# ProPrj_51board_2024-12-11.net
KiCad netlist of a schematic drawn in EasyEDA Pro
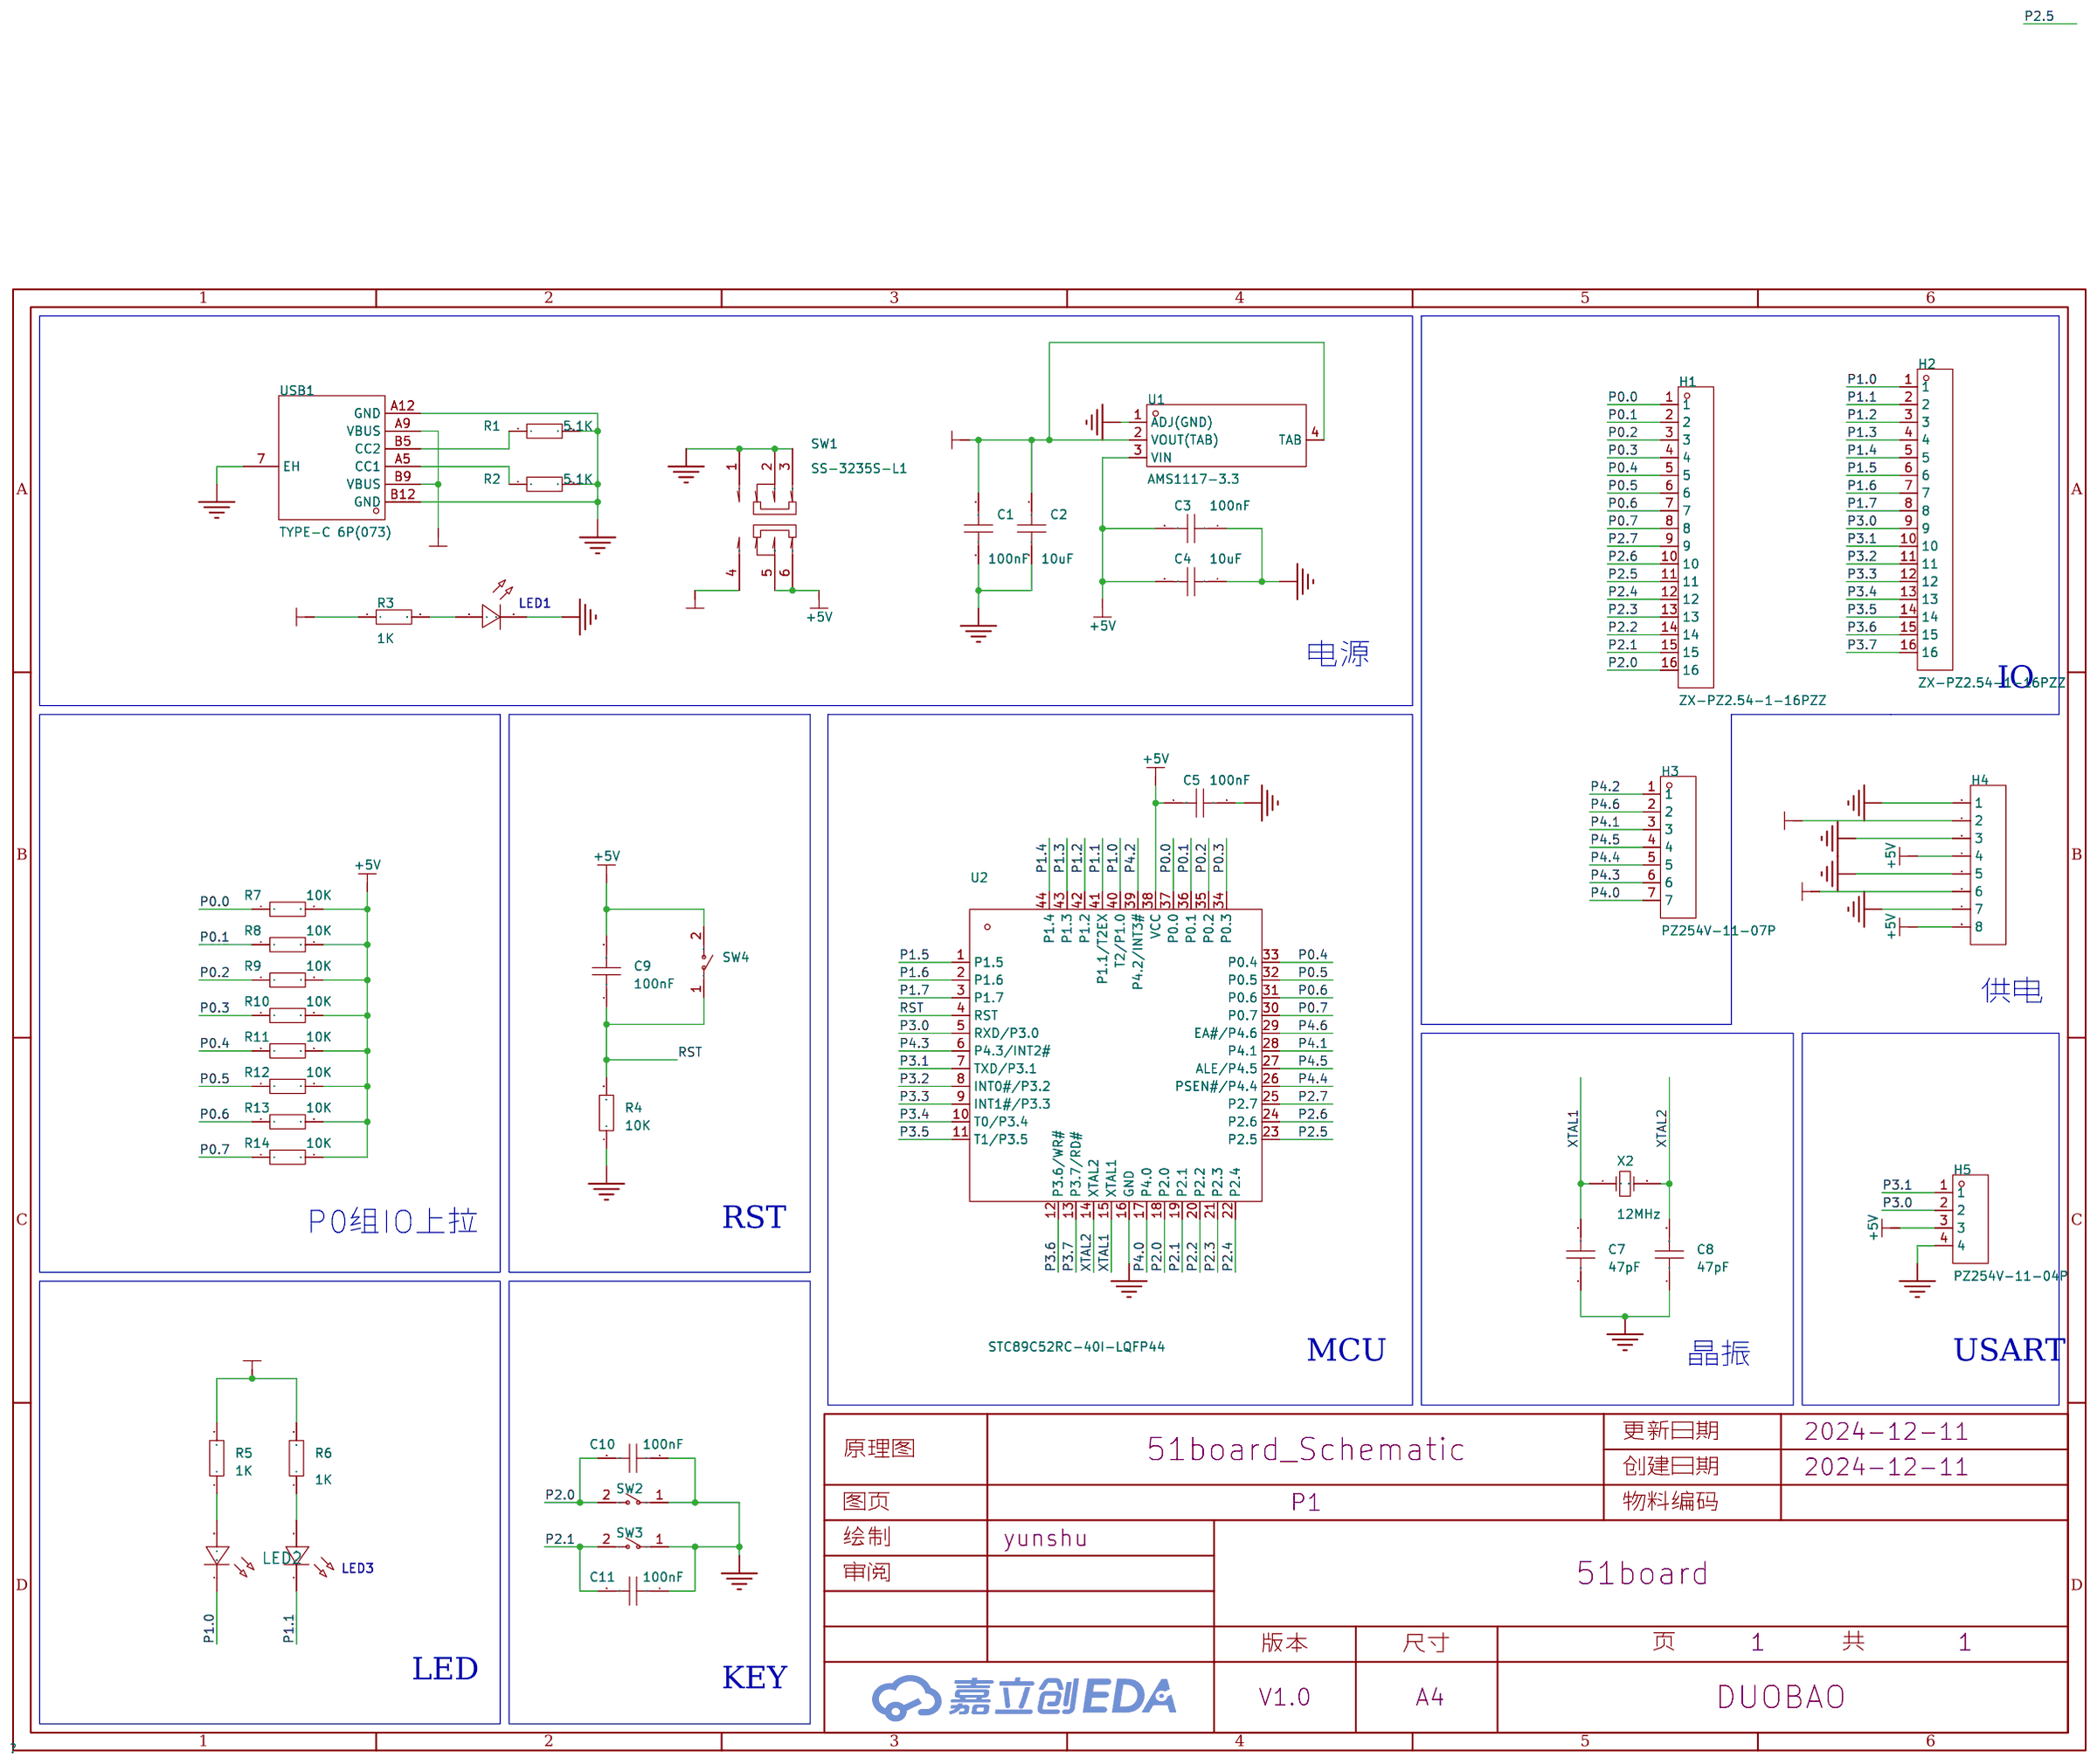
[diagram p0: schematic sheet]

(export (version "E")
  (design (tool "Eeschema 10.0.6"))
  (components
    (comp (ref "C1")
      (value "100nF")
      (footprint "easyedapro:C0603")
      (libsource (lib "easyedapro") (part "CapAcitance"))
    )
    (comp (ref "C2")
      (value "10uF")
      (footprint "easyedapro:C0603")
      (libsource (lib "easyedapro") (part "CapAcitance"))
    )
    (comp (ref "C3")
      (value "100nF")
      (footprint "easyedapro:C0603")
      (libsource (lib "easyedapro") (part "CapAcitance"))
    )
    (comp (ref "C4")
      (value "10uF")
      (footprint "easyedapro:C0603")
      (libsource (lib "easyedapro") (part "CapAcitance"))
    )
    (comp (ref "C5")
      (value "100nF")
      (footprint "easyedapro:C0603")
      (libsource (lib "easyedapro") (part "CapAcitance"))
    )
    (comp (ref "C7")
      (value "47pF")
      (footprint "easyedapro:C0603")
      (libsource (lib "easyedapro") (part "CapAcitance"))
    )
    (comp (ref "C8")
      (value "47pF")
      (footprint "easyedapro:C0603")
      (libsource (lib "easyedapro") (part "CapAcitance"))
    )
    (comp (ref "C9")
      (value "100nF")
      (footprint "easyedapro:C0603")
      (libsource (lib "easyedapro") (part "CapAcitance"))
    )
    (comp (ref "C10")
      (value "100nF")
      (footprint "easyedapro:C0603")
      (libsource (lib "easyedapro") (part "CapAcitance"))
    )
    (comp (ref "C11")
      (value "100nF")
      (footprint "easyedapro:C0603")
      (libsource (lib "easyedapro") (part "CapAcitance"))
    )
    (comp (ref "H1")
      (value "ZX-PZ2.54-1-16PZZ")
      (footprint "easyedapro:HDR-TH_16P-P2.54-V-M")
      (fields (field (name "Manufacturer") "Megastar(兆星)"))
      (libsource (lib "easyedapro") (part "HDR_2.54-1x16P"))
    )
    (comp (ref "H2")
      (value "ZX-PZ2.54-1-16PZZ")
      (footprint "easyedapro:HDR-TH_16P-P2.54-V-M")
      (fields (field (name "Manufacturer") "Megastar(兆星)"))
      (libsource (lib "easyedapro") (part "HDR_2.54-1x16P"))
    )
    (comp (ref "H3")
      (value "PZ254V-11-07P")
      (footprint "easyedapro:HDR-TH_7P-P2.54-V-M")
      (fields (field (name "Manufacturer") "XFCN(兴飞)"))
      (libsource (lib "easyedapro") (part "PZ254V-11-07P"))
    )
    (comp (ref "H4")
      (value "~")
      (footprint "easyedapro:HDR-TH_8P-P2.54-V-F-1")
      (libsource (lib "easyedapro") (part "Header-Female-2.54_1x8"))
    )
    (comp (ref "H5")
      (value "PZ254V-11-04P")
      (footprint "easyedapro:HDR-TH_4P-P2.54-V-M")
      (fields (field (name "Manufacturer") "XFCN(兴飞)"))
      (libsource (lib "easyedapro") (part "PZ254V-11-04P"))
    )
    (comp (ref "LED1")
      (value "~")
      (footprint "easyedapro:LED_0805")
      (libsource (lib "easyedapro") (part "LED_G"))
    )
    (comp (ref "LED2")
      (value "~")
      (footprint "easyedapro:LED_0805")
      (libsource (lib "easyedapro") (part "LED_R"))
    )
    (comp (ref "LED3")
      (value "~")
      (footprint "easyedapro:LED_0805")
      (libsource (lib "easyedapro") (part "LED_B"))
    )
    (comp (ref "R1") (value "5.1K") (footprint "easyedapro:R0805") (libsource (lib "easyedapro") (part "电阻")))
    (comp (ref "R2") (value "5.1K") (footprint "easyedapro:R0805") (libsource (lib "easyedapro") (part "电阻")))
    (comp (ref "R3") (value "1K") (footprint "easyedapro:R0805") (libsource (lib "easyedapro") (part "电阻")))
    (comp (ref "R4") (value "10K") (footprint "easyedapro:R0805") (libsource (lib "easyedapro") (part "电阻")))
    (comp (ref "R5") (value "1K") (footprint "easyedapro:R0805") (libsource (lib "easyedapro") (part "电阻")))
    (comp (ref "R6") (value "1K") (footprint "easyedapro:R0805") (libsource (lib "easyedapro") (part "电阻")))
    (comp (ref "R7") (value "10K") (footprint "easyedapro:R0805") (libsource (lib "easyedapro") (part "电阻")))
    (comp (ref "R8") (value "10K") (footprint "easyedapro:R0805") (libsource (lib "easyedapro") (part "电阻")))
    (comp (ref "R9") (value "10K") (footprint "easyedapro:R0805") (libsource (lib "easyedapro") (part "电阻")))
    (comp (ref "R10") (value "10K") (footprint "easyedapro:R0805") (libsource (lib "easyedapro") (part "电阻")))
    (comp (ref "R11") (value "10K") (footprint "easyedapro:R0805") (libsource (lib "easyedapro") (part "电阻")))
    (comp (ref "R12") (value "10K") (footprint "easyedapro:R0805") (libsource (lib "easyedapro") (part "电阻")))
    (comp (ref "R13") (value "10K") (footprint "easyedapro:R0805") (libsource (lib "easyedapro") (part "电阻")))
    (comp (ref "R14") (value "10K") (footprint "easyedapro:R0805") (libsource (lib "easyedapro") (part "电阻")))
    (comp (ref "SW1")
      (value "SS-3235S-L1")
      (footprint "easyedapro:SW-SMD_SS-3235S-LX")
      (description "电路结构:双刀双掷;安装方式:卧贴;开关颜色:黑色;额定电流(DC):50mA;额定电压(DC):12V;额定电流(AC):50mA;额定电压(AC):12V;机械寿命:1万次;")
      (fields (field (name "Manufacturer") "XKB Connectivity(中国星坤)"))
      (libsource (lib "easyedapro") (part "SS-3235S-L1"))
    )
    (comp (ref "SW2")
      (value "轻触按键 3x6x2.5mm")
      (footprint "easyedapro:SW-SMD_L6.1-W3.7-LS8.0")
      (description "开关长度:6.05mm;开关宽度:3.65mm;开关高度:2.5mm;机械寿命:-;")
      (fields (field (name "Manufacturer") "BBJ"))
      (libsource (lib "easyedapro") (part "轻触按键 3X6X2.5MM"))
    )
    (comp (ref "SW3")
      (value "轻触按键 3x6x2.5mm")
      (footprint "easyedapro:SW-SMD_L6.1-W3.7-LS8.0")
      (description "开关长度:6.05mm;开关宽度:3.65mm;开关高度:2.5mm;机械寿命:-;")
      (fields (field (name "Manufacturer") "BBJ"))
      (libsource (lib "easyedapro") (part "轻触按键 3X6X2.5MM"))
    )
    (comp (ref "SW4")
      (value "轻触按键 3x6x2.5mm")
      (footprint "easyedapro:SW-SMD_L6.1-W3.7-LS8.0")
      (description "开关长度:6.05mm;开关宽度:3.65mm;开关高度:2.5mm;机械寿命:-;")
      (fields (field (name "Manufacturer") "BBJ"))
      (libsource (lib "easyedapro") (part "轻触按键 3X6X2.5MM"))
    )
    (comp (ref "U1")
      (value "AMS1117-3.3")
      (footprint "easyedapro:SOT-223-4_L6.5-W3.5-P2.30-LS7.0-BR")
      (description "输出类型:固定;最大输入电压:18V;输出电压:3.3V;输出电流:1A;电源纹波抑制比(PSRR):60dB@(120Hz);输出极性:正极;")
      (fields (field (name "Manufacturer") "UMW(友台半导体)"))
      (libsource (lib "easyedapro") (part "AMS1117-3.3_C347222"))
    )
    (comp (ref "U2")
      (value "STC89C52RC-40I-LQFP44")
      (footprint "easyedapro:LQFP-44_L10.0-W10.0-P0.80-LS12.0-BL")
      (description "CPU内核:51系列;程序存储容量:8KB;RAM总容量:512Byte;GPIO端口数量:39;工作电压范围:3.3V~5.5V;CPU最大主频:-;程序存储器类型:FLASH;")
      (fields (field (name "Manufacturer") "STC(宏晶)"))
      (libsource (lib "easyedapro") (part "STC89C52RC-40I_C8707"))
    )
    (comp (ref "USB1")
      (value "TYPE-C 6P(073)")
      (footprint "easyedapro:TYPE-C-SMD_TYPE-C-6P_5")
      (description "连接器类型:Type-C;标准:USB 3.1;公母:母;安装方式:卧贴;触点数量:6P;端口数量:1;额定电流 - 电源:3A;工作温度范围:-25°C~+85°C;")
      (fields (field (name "Manufacturer") "SHOU HAN(首韩)"))
      (libsource (lib "easyedapro") (part "TYPE-C 6P(073)"))
    )
    (comp (ref "X2")
      (value "12MHz")
      (footprint "easyedapro:OSC-TH_BD2.0-P0.50")
      (description "晶振类型:直插晶振;频率:12MHz;常温频差:±20ppm;外接负载电容:20pF;频率稳定度(全温):±30ppm;")
      (fields
        (field (name "Manufacturer Part") "TXD12M0002206LDBEO00S")
        (field (name "Manufacturer") "YJX(雅晶鑫)")
      )
      (libsource (lib "easyedapro") (part "TXD12M0002206LDBEO00S"))
    )
  )
  (nets
    (net (code "1") (name "+5V") (class "Default")
      (node (ref "C3") (pin "2") (pinfunction "2_2") (pintype "input"))
      (node (ref "C4") (pin "2") (pinfunction "2_2") (pintype "input"))
      (node (ref "C5") (pin "1") (pinfunction "1_1") (pintype "input"))
      (node (ref "C9") (pin "2") (pinfunction "2_2") (pintype "input"))
      (node (ref "H4") (pin "4") (pinfunction "4_4") (pintype "input"))
      (node (ref "H4") (pin "8") (pinfunction "8_8") (pintype "input"))
      (node (ref "H5") (pin "3") (pinfunction "3_3") (pintype "unspecified"))
      (node (ref "R10") (pin "2") (pinfunction "2_2") (pintype "input"))
      (node (ref "R11") (pin "2") (pinfunction "2_2") (pintype "input"))
      (node (ref "R12") (pin "2") (pinfunction "2_2") (pintype "input"))
      (node (ref "R13") (pin "2") (pinfunction "2_2") (pintype "input"))
      (node (ref "R14") (pin "2") (pinfunction "2_2") (pintype "input"))
      (node (ref "R7") (pin "2") (pinfunction "2_2") (pintype "input"))
      (node (ref "R8") (pin "2") (pinfunction "2_2") (pintype "input"))
      (node (ref "R9") (pin "2") (pinfunction "2_2") (pintype "input"))
      (node (ref "SW1") (pin "5") (pinfunction "5_5") (pintype "unspecified"))
      (node (ref "SW1") (pin "6") (pinfunction "6_6") (pintype "unspecified"))
      (node (ref "SW4") (pin "2") (pinfunction "2_2") (pintype "unspecified"))
      (node (ref "U1") (pin "3") (pinfunction "VIN_3") (pintype "unspecified"))
      (node (ref "U2") (pin "38") (pinfunction "VCC_38") (pintype "unspecified"))
    )
    (net (code "2") (name "/P0.0") (class "Default")
      (node (ref "H1") (pin "1") (pinfunction "1_1") (pintype "input"))
      (node (ref "R7") (pin "1") (pinfunction "1_1") (pintype "input"))
      (node (ref "U2") (pin "37") (pinfunction "P0.0_37") (pintype "unspecified"))
    )
    (net (code "3") (name "/P0.1") (class "Default")
      (node (ref "H1") (pin "2") (pinfunction "2_2") (pintype "input"))
      (node (ref "R8") (pin "1") (pinfunction "1_1") (pintype "input"))
      (node (ref "U2") (pin "36") (pinfunction "P0.1_36") (pintype "unspecified"))
    )
    (net (code "4") (name "/P0.2") (class "Default")
      (node (ref "H1") (pin "3") (pinfunction "3_3") (pintype "input"))
      (node (ref "R9") (pin "1") (pinfunction "1_1") (pintype "input"))
      (node (ref "U2") (pin "35") (pinfunction "P0.2_35") (pintype "unspecified"))
    )
    (net (code "5") (name "/P0.3") (class "Default")
      (node (ref "H1") (pin "4") (pinfunction "4_4") (pintype "input"))
      (node (ref "R10") (pin "1") (pinfunction "1_1") (pintype "input"))
      (node (ref "U2") (pin "34") (pinfunction "P0.3_34") (pintype "unspecified"))
    )
    (net (code "6") (name "/P0.4") (class "Default")
      (node (ref "H1") (pin "5") (pinfunction "5_5") (pintype "input"))
      (node (ref "R11") (pin "1") (pinfunction "1_1") (pintype "input"))
      (node (ref "U2") (pin "33") (pinfunction "P0.4_33") (pintype "unspecified"))
    )
    (net (code "7") (name "/P0.5") (class "Default")
      (node (ref "H1") (pin "6") (pinfunction "6_6") (pintype "input"))
      (node (ref "R12") (pin "1") (pinfunction "1_1") (pintype "input"))
      (node (ref "U2") (pin "32") (pinfunction "P0.5_32") (pintype "unspecified"))
    )
    (net (code "8") (name "/P0.6") (class "Default")
      (node (ref "H1") (pin "7") (pinfunction "7_7") (pintype "input"))
      (node (ref "R13") (pin "1") (pinfunction "1_1") (pintype "input"))
      (node (ref "U2") (pin "31") (pinfunction "P0.6_31") (pintype "unspecified"))
    )
    (net (code "9") (name "/P0.7") (class "Default")
      (node (ref "H1") (pin "8") (pinfunction "8_8") (pintype "input"))
      (node (ref "R14") (pin "1") (pinfunction "1_1") (pintype "input"))
      (node (ref "U2") (pin "30") (pinfunction "P0.7_30") (pintype "unspecified"))
    )
    (net (code "10") (name "/P1.0") (class "Default")
      (node (ref "H2") (pin "1") (pinfunction "1_1") (pintype "input"))
      (node (ref "LED2") (pin "1") (pinfunction "C_1") (pintype "input"))
      (node (ref "U2") (pin "40") (pinfunction "T2/P1.0_40") (pintype "unspecified"))
    )
    (net (code "11") (name "/P1.1") (class "Default")
      (node (ref "H2") (pin "2") (pinfunction "2_2") (pintype "input"))
      (node (ref "LED3") (pin "1") (pinfunction "C_1") (pintype "input"))
      (node (ref "U2") (pin "41") (pinfunction "P1.1/T2EX_41") (pintype "unspecified"))
    )
    (net (code "12") (name "/P1.2") (class "Default")
      (node (ref "H2") (pin "3") (pinfunction "3_3") (pintype "input"))
      (node (ref "U2") (pin "42") (pinfunction "P1.2_42") (pintype "unspecified"))
    )
    (net (code "13") (name "/P1.3") (class "Default")
      (node (ref "H2") (pin "4") (pinfunction "4_4") (pintype "input"))
      (node (ref "U2") (pin "43") (pinfunction "P1.3_43") (pintype "unspecified"))
    )
    (net (code "14") (name "/P1.4") (class "Default")
      (node (ref "H2") (pin "5") (pinfunction "5_5") (pintype "input"))
      (node (ref "U2") (pin "44") (pinfunction "P1.4_44") (pintype "unspecified"))
    )
    (net (code "15") (name "/P1.5") (class "Default")
      (node (ref "H2") (pin "6") (pinfunction "6_6") (pintype "input"))
      (node (ref "U2") (pin "1") (pinfunction "P1.5_1") (pintype "unspecified"))
    )
    (net (code "16") (name "/P1.6") (class "Default")
      (node (ref "H2") (pin "7") (pinfunction "7_7") (pintype "input"))
      (node (ref "U2") (pin "2") (pinfunction "P1.6_2") (pintype "unspecified"))
    )
    (net (code "17") (name "/P1.7") (class "Default")
      (node (ref "H2") (pin "8") (pinfunction "8_8") (pintype "input"))
      (node (ref "U2") (pin "3") (pinfunction "P1.7_3") (pintype "unspecified"))
    )
    (net (code "18") (name "/P2.0") (class "Default")
      (node (ref "C10") (pin "2") (pinfunction "2_2") (pintype "input"))
      (node (ref "H1") (pin "16") (pinfunction "16_16") (pintype "input"))
      (node (ref "SW2") (pin "2") (pinfunction "2_2") (pintype "unspecified"))
      (node (ref "U2") (pin "18") (pinfunction "P2.0_18") (pintype "unspecified"))
    )
    (net (code "19") (name "/P2.1") (class "Default")
      (node (ref "C11") (pin "2") (pinfunction "2_2") (pintype "input"))
      (node (ref "H1") (pin "15") (pinfunction "15_15") (pintype "input"))
      (node (ref "SW3") (pin "2") (pinfunction "2_2") (pintype "unspecified"))
      (node (ref "U2") (pin "19") (pinfunction "P2.1_19") (pintype "unspecified"))
    )
    (net (code "20") (name "/P2.2") (class "Default")
      (node (ref "H1") (pin "14") (pinfunction "14_14") (pintype "input"))
      (node (ref "U2") (pin "20") (pinfunction "P2.2_20") (pintype "unspecified"))
    )
    (net (code "21") (name "/P2.3") (class "Default")
      (node (ref "H1") (pin "13") (pinfunction "13_13") (pintype "input"))
      (node (ref "U2") (pin "21") (pinfunction "P2.3_21") (pintype "unspecified"))
    )
    (net (code "22") (name "/P2.4") (class "Default")
      (node (ref "H1") (pin "12") (pinfunction "12_12") (pintype "input"))
      (node (ref "U2") (pin "22") (pinfunction "P2.4_22") (pintype "unspecified"))
    )
    (net (code "23") (name "/P2.5") (class "Default")
      (node (ref "H1") (pin "11") (pinfunction "11_11") (pintype "input"))
      (node (ref "U2") (pin "23") (pinfunction "P2.5_23") (pintype "unspecified"))
    )
    (net (code "24") (name "/P2.6") (class "Default")
      (node (ref "H1") (pin "10") (pinfunction "10_10") (pintype "input"))
      (node (ref "U2") (pin "24") (pinfunction "P2.6_24") (pintype "unspecified"))
    )
    (net (code "25") (name "/P2.7") (class "Default")
      (node (ref "H1") (pin "9") (pinfunction "9_9") (pintype "input"))
      (node (ref "U2") (pin "25") (pinfunction "P2.7_25") (pintype "unspecified"))
    )
    (net (code "26") (name "/P3.0") (class "Default")
      (node (ref "H2") (pin "9") (pinfunction "9_9") (pintype "input"))
      (node (ref "H5") (pin "2") (pinfunction "2_2") (pintype "unspecified"))
      (node (ref "U2") (pin "5") (pinfunction "RXD/P3.0_5") (pintype "unspecified"))
    )
    (net (code "27") (name "/P3.1") (class "Default")
      (node (ref "H2") (pin "10") (pinfunction "10_10") (pintype "input"))
      (node (ref "H5") (pin "1") (pinfunction "1_1") (pintype "unspecified"))
      (node (ref "U2") (pin "7") (pinfunction "TXD/P3.1_7") (pintype "unspecified"))
    )
    (net (code "28") (name "/P3.2") (class "Default")
      (node (ref "H2") (pin "11") (pinfunction "11_11") (pintype "input"))
      (node (ref "U2") (pin "8") (pinfunction "INT0#/P3.2_8") (pintype "unspecified"))
    )
    (net (code "29") (name "/P3.3") (class "Default")
      (node (ref "H2") (pin "12") (pinfunction "12_12") (pintype "input"))
      (node (ref "U2") (pin "9") (pinfunction "INT1#/P3.3_9") (pintype "unspecified"))
    )
    (net (code "30") (name "/P3.4") (class "Default")
      (node (ref "H2") (pin "13") (pinfunction "13_13") (pintype "input"))
      (node (ref "U2") (pin "10") (pinfunction "T0/P3.4_10") (pintype "unspecified"))
    )
    (net (code "31") (name "/P3.5") (class "Default")
      (node (ref "H2") (pin "14") (pinfunction "14_14") (pintype "input"))
      (node (ref "U2") (pin "11") (pinfunction "T1/P3.5_11") (pintype "unspecified"))
    )
    (net (code "32") (name "/P3.6") (class "Default")
      (node (ref "H2") (pin "15") (pinfunction "15_15") (pintype "input"))
      (node (ref "U2") (pin "12") (pinfunction "P3.6/WR#_12") (pintype "unspecified"))
    )
    (net (code "33") (name "/P3.7") (class "Default")
      (node (ref "H2") (pin "16") (pinfunction "16_16") (pintype "input"))
      (node (ref "U2") (pin "13") (pinfunction "P3.7/RD#_13") (pintype "unspecified"))
    )
    (net (code "34") (name "/P4.0") (class "Default")
      (node (ref "H3") (pin "7") (pinfunction "7_7") (pintype "unspecified"))
      (node (ref "U2") (pin "17") (pinfunction "P4.0_17") (pintype "unspecified"))
    )
    (net (code "35") (name "/P4.1") (class "Default")
      (node (ref "H3") (pin "3") (pinfunction "3_3") (pintype "unspecified"))
      (node (ref "U2") (pin "28") (pinfunction "P4.1_28") (pintype "unspecified"))
    )
    (net (code "36") (name "/P4.2") (class "Default")
      (node (ref "H3") (pin "1") (pinfunction "1_1") (pintype "unspecified"))
      (node (ref "U2") (pin "39") (pinfunction "P4.2/INT3#_39") (pintype "unspecified"))
    )
    (net (code "37") (name "/P4.3") (class "Default")
      (node (ref "H3") (pin "6") (pinfunction "6_6") (pintype "unspecified"))
      (node (ref "U2") (pin "6") (pinfunction "P4.3/INT2#_6") (pintype "unspecified"))
    )
    (net (code "38") (name "/P4.4") (class "Default")
      (node (ref "H3") (pin "5") (pinfunction "5_5") (pintype "unspecified"))
      (node (ref "U2") (pin "26") (pinfunction "PSEN#/P4.4_26") (pintype "unspecified"))
    )
    (net (code "39") (name "/P4.5") (class "Default")
      (node (ref "H3") (pin "4") (pinfunction "4_4") (pintype "unspecified"))
      (node (ref "U2") (pin "27") (pinfunction "ALE/P4.5_27") (pintype "unspecified"))
    )
    (net (code "40") (name "/P4.6") (class "Default")
      (node (ref "H3") (pin "2") (pinfunction "2_2") (pintype "unspecified"))
      (node (ref "U2") (pin "29") (pinfunction "EA#/P4.6_29") (pintype "unspecified"))
    )
    (net (code "41") (name "/RST") (class "Default")
      (node (ref "C9") (pin "1") (pinfunction "1_1") (pintype "input"))
      (node (ref "R4") (pin "2") (pinfunction "2_2") (pintype "input"))
      (node (ref "SW4") (pin "1") (pinfunction "1_1") (pintype "unspecified"))
      (node (ref "U2") (pin "4") (pinfunction "RST_4") (pintype "unspecified"))
    )
    (net (code "42") (name "/XTAL1") (class "Default")
      (node (ref "C7") (pin "2") (pinfunction "2_2") (pintype "input"))
      (node (ref "U2") (pin "15") (pinfunction "XTAL1_15") (pintype "unspecified"))
      (node (ref "X2") (pin "1") (pinfunction "OSC1_1") (pintype "unspecified"))
    )
    (net (code "43") (name "/XTAL2") (class "Default")
      (node (ref "C8") (pin "2") (pinfunction "2_2") (pintype "input"))
      (node (ref "U2") (pin "14") (pinfunction "XTAL2_14") (pintype "unspecified"))
      (node (ref "X2") (pin "2") (pinfunction "OSC2_2") (pintype "unspecified"))
    )
    (net (code "44") (name "GND") (class "Default")
      (node (ref "C1") (pin "2") (pinfunction "2_2") (pintype "input"))
      (node (ref "C10") (pin "1") (pinfunction "1_1") (pintype "input"))
      (node (ref "C11") (pin "1") (pinfunction "1_1") (pintype "input"))
      (node (ref "C2") (pin "2") (pinfunction "2_2") (pintype "input"))
      (node (ref "C3") (pin "1") (pinfunction "1_1") (pintype "input"))
      (node (ref "C4") (pin "1") (pinfunction "1_1") (pintype "input"))
      (node (ref "C5") (pin "2") (pinfunction "2_2") (pintype "input"))
      (node (ref "C7") (pin "1") (pinfunction "1_1") (pintype "input"))
      (node (ref "C8") (pin "1") (pinfunction "1_1") (pintype "input"))
      (node (ref "H4") (pin "1") (pinfunction "1_1") (pintype "input"))
      (node (ref "H4") (pin "3") (pinfunction "3_3") (pintype "input"))
      (node (ref "H4") (pin "5") (pinfunction "5_5") (pintype "input"))
      (node (ref "H4") (pin "7") (pinfunction "7_7") (pintype "input"))
      (node (ref "H5") (pin "4") (pinfunction "4_4") (pintype "unspecified"))
      (node (ref "LED1") (pin "1") (pinfunction "C_1") (pintype "input"))
      (node (ref "R1") (pin "2") (pinfunction "2_2") (pintype "input"))
      (node (ref "R2") (pin "2") (pinfunction "2_2") (pintype "input"))
      (node (ref "R4") (pin "1") (pinfunction "1_1") (pintype "input"))
      (node (ref "SW1") (pin "1") (pinfunction "1_1") (pintype "unspecified"))
      (node (ref "SW1") (pin "2") (pinfunction "2_2") (pintype "unspecified"))
      (node (ref "SW1") (pin "3") (pinfunction "3_3") (pintype "unspecified"))
      (node (ref "SW2") (pin "1") (pinfunction "1_1") (pintype "unspecified"))
      (node (ref "SW3") (pin "1") (pinfunction "1_1") (pintype "unspecified"))
      (node (ref "U1") (pin "1") (pinfunction "ADJ(GND)_1") (pintype "unspecified"))
      (node (ref "U2") (pin "16") (pinfunction "GND_16") (pintype "unspecified"))
      (node (ref "USB1") (pin "7") (pinfunction "EH_7") (pintype "unspecified"))
      (node (ref "USB1") (pin "A12") (pinfunction "GND_A12") (pintype "unspecified"))
      (node (ref "USB1") (pin "B12") (pinfunction "GND_B12") (pintype "unspecified"))
    )
    (net (code "45") (name "Net-(LED1-A)") (class "Default")
      (node (ref "LED1") (pin "2") (pinfunction "A_2") (pintype "input"))
      (node (ref "R3") (pin "2") (pinfunction "2_2") (pintype "input"))
    )
    (net (code "46") (name "Net-(LED2-A)") (class "Default")
      (node (ref "LED2") (pin "2") (pinfunction "A_2") (pintype "input"))
      (node (ref "R5") (pin "1") (pinfunction "1_1") (pintype "input"))
    )
    (net (code "47") (name "Net-(LED3-A)") (class "Default")
      (node (ref "LED3") (pin "2") (pinfunction "A_2") (pintype "input"))
      (node (ref "R6") (pin "1") (pinfunction "1_1") (pintype "input"))
    )
    (net (code "48") (name "Net-(USB1-CC1)") (class "Default")
      (node (ref "R2") (pin "1") (pinfunction "1_1") (pintype "input"))
      (node (ref "USB1") (pin "A5") (pinfunction "CC1_A5") (pintype "unspecified"))
    )
    (net (code "49") (name "Net-(USB1-CC2)") (class "Default")
      (node (ref "R1") (pin "1") (pinfunction "1_1") (pintype "input"))
      (node (ref "USB1") (pin "B5") (pinfunction "CC2_B5") (pintype "unspecified"))
    )
    (net (code "50") (name "VCC+3.3V") (class "Default")
      (node (ref "C1") (pin "1") (pinfunction "1_1") (pintype "input"))
      (node (ref "C2") (pin "1") (pinfunction "1_1") (pintype "input"))
      (node (ref "H4") (pin "2") (pinfunction "2_2") (pintype "input"))
      (node (ref "H4") (pin "6") (pinfunction "6_6") (pintype "input"))
      (node (ref "R3") (pin "1") (pinfunction "1_1") (pintype "input"))
      (node (ref "R5") (pin "2") (pinfunction "2_2") (pintype "input"))
      (node (ref "R6") (pin "2") (pinfunction "2_2") (pintype "input"))
      (node (ref "U1") (pin "2") (pinfunction "VOUT(TAB)_2") (pintype "unspecified"))
      (node (ref "U1") (pin "4") (pinfunction "TAB_4") (pintype "unspecified"))
    )
    (net (code "51") (name "VCC+5V") (class "Default")
      (node (ref "SW1") (pin "4") (pinfunction "4_4") (pintype "unspecified"))
      (node (ref "USB1") (pin "A9") (pinfunction "VBUS_A9") (pintype "unspecified"))
      (node (ref "USB1") (pin "B9") (pinfunction "VBUS_B9") (pintype "unspecified"))
    )
  )
)
